# 3_shkb_downstream_con.net
KiCad netlist of a schematic drawn in Altium Designer
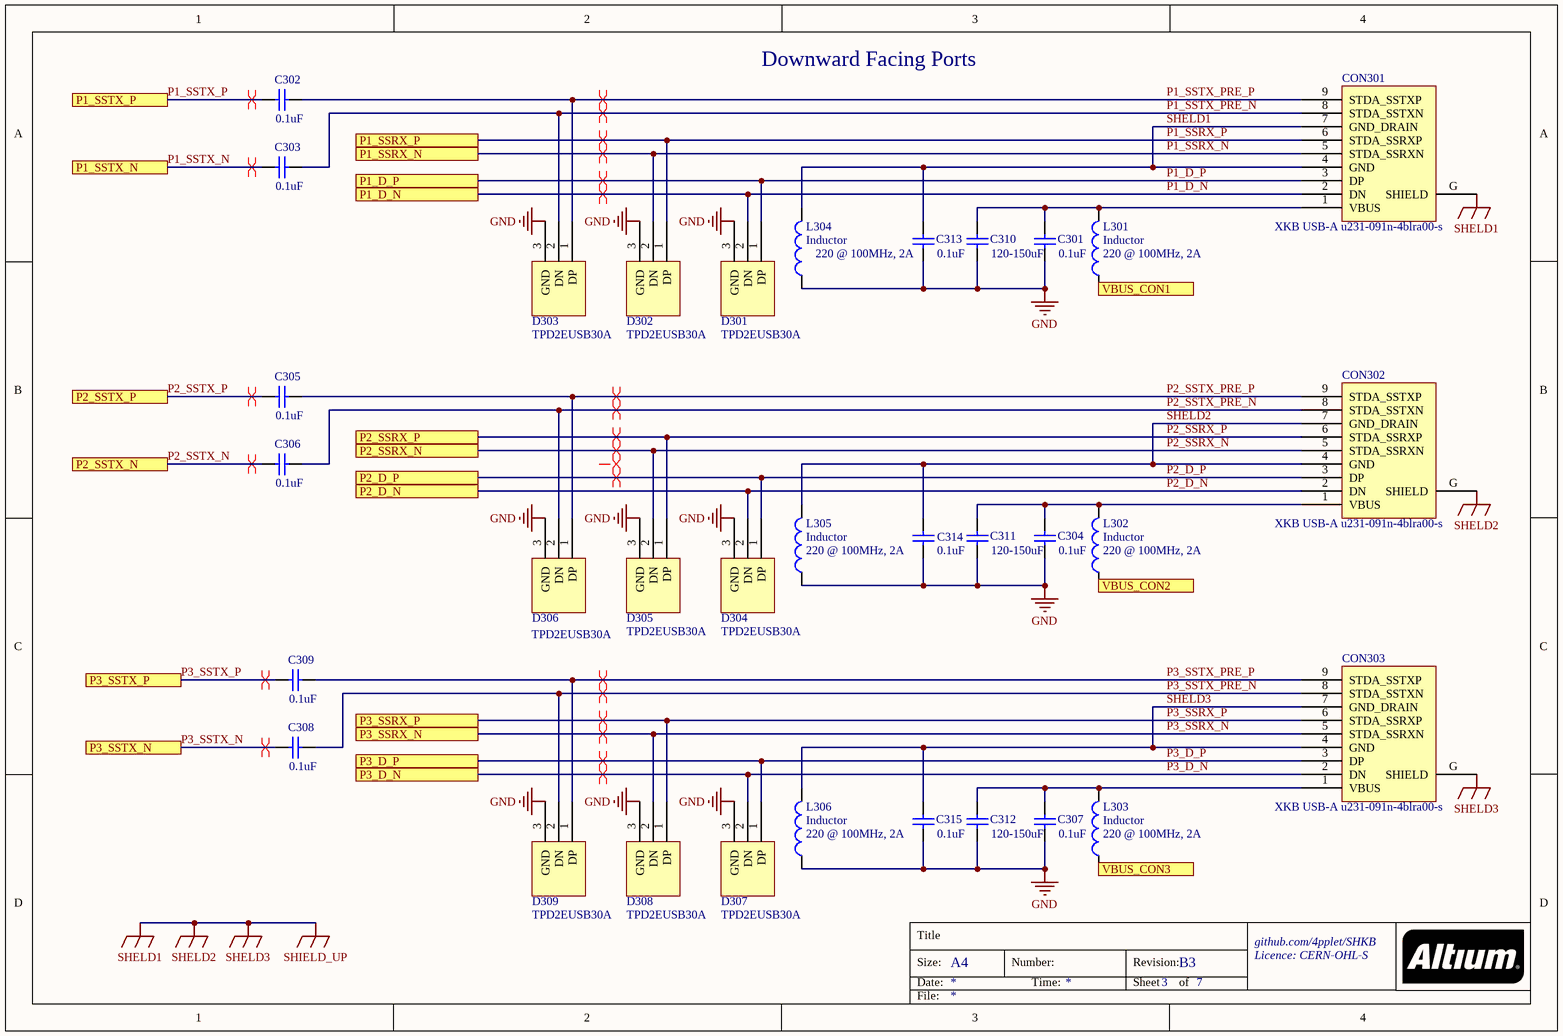
[diagram p0: 3_shkb_downstream_con.SchDoc]

(export (version "E")
  (design (tool "Eeschema 10.0.6"))
  (components
    (comp (ref "C301")
      (value "0.1uF")
      (footprint "C0603[1608]")
      (description "Capacitor")
      (fields (field (name "MFG") "KEMET") (field (name "LCSC PART #") "C14663"))
      (libsource (lib "Miscellaneous Devices") (part "Cap"))
    )
    (comp (ref "C302")
      (value "0.1uF")
      (footprint "C0402[1005]")
      (description "Capacitor")
      (fields (field (name "MFG") "KEMET") (field (name "LCSC PART #") "C1525"))
      (libsource (lib "Miscellaneous Devices") (part "Cap"))
    )
    (comp (ref "C303")
      (value "0.1uF")
      (footprint "C0402[1005]")
      (description "Capacitor")
      (fields (field (name "MFG") "KEMET") (field (name "LCSC PART #") "C1525"))
      (libsource (lib "Miscellaneous Devices") (part "Cap"))
    )
    (comp (ref "C304")
      (value "0.1uF")
      (footprint "C0603[1608]")
      (description "Capacitor")
      (fields (field (name "MFG") "KEMET") (field (name "LCSC PART #") "C14663"))
      (libsource (lib "Miscellaneous Devices") (part "Cap"))
    )
    (comp (ref "C305")
      (value "0.1uF")
      (footprint "C0402[1005]")
      (description "Capacitor")
      (fields (field (name "MFG") "KEMET") (field (name "LCSC PART #") "C1525"))
      (libsource (lib "Miscellaneous Devices") (part "Cap"))
    )
    (comp (ref "C306")
      (value "0.1uF")
      (footprint "C0402[1005]")
      (description "Capacitor")
      (fields (field (name "MFG") "KEMET") (field (name "LCSC PART #") "C1525"))
      (libsource (lib "Miscellaneous Devices") (part "Cap"))
    )
    (comp (ref "C307")
      (value "0.1uF")
      (footprint "C0603[1608]")
      (description "Capacitor")
      (fields (field (name "MFG") "KEMET") (field (name "LCSC PART #") "C14663"))
      (libsource (lib "Miscellaneous Devices") (part "Cap"))
    )
    (comp (ref "C308")
      (value "0.1uF")
      (footprint "C0402[1005]")
      (description "Capacitor")
      (fields (field (name "MFG") "KEMET") (field (name "LCSC PART #") "C1525"))
      (libsource (lib "Miscellaneous Devices") (part "Cap"))
    )
    (comp (ref "C309")
      (value "0.1uF")
      (footprint "C0402[1005]")
      (description "Capacitor")
      (fields (field (name "MFG") "KEMET") (field (name "LCSC PART #") "C1525"))
      (libsource (lib "Miscellaneous Devices") (part "Cap"))
    )
    (comp (ref "C310")
      (value "120-150uF")
      (footprint "C_9L_9M")
      (description "Capacitor")
      (fields (field (name "MRF.PART") "XT100UF16V90RV0074") (field (name "LCSC PART #") "C2992605"))
      (libsource (lib "Miscellaneous Devices") (part "Cap"))
    )
    (comp (ref "C311")
      (value "120-150uF")
      (footprint "C_9L_9M")
      (description "Capacitor")
      (fields (field (name "MRF.PART") "XT100UF16V90RV0074") (field (name "LCSC PART #") "C2992605"))
      (libsource (lib "Miscellaneous Devices") (part "Cap"))
    )
    (comp (ref "C312")
      (value "120-150uF")
      (footprint "C_9L_9M")
      (description "Capacitor")
      (fields (field (name "MRF.PART") "XT100UF16V90RV0074") (field (name "LCSC PART #") "C2992605"))
      (libsource (lib "Miscellaneous Devices") (part "Cap"))
    )
    (comp (ref "C313")
      (value "0.1uF")
      (footprint "C0603[1608]")
      (description "Capacitor")
      (fields (field (name "MFG") "KEMET") (field (name "LCSC PART #") "C14663"))
      (libsource (lib "Miscellaneous Devices") (part "Cap"))
    )
    (comp (ref "C314")
      (value "0.1uF")
      (footprint "C0603[1608]")
      (description "Capacitor")
      (fields (field (name "MFG") "KEMET") (field (name "LCSC PART #") "C14663"))
      (libsource (lib "Miscellaneous Devices") (part "Cap"))
    )
    (comp (ref "C315")
      (value "0.1uF")
      (footprint "C0603[1608]")
      (description "Capacitor")
      (fields (field (name "MFG") "KEMET") (field (name "LCSC PART #") "C14663"))
      (libsource (lib "Miscellaneous Devices") (part "Cap"))
    )
    (comp (ref "CON301")
      (value "XKB USB-A u231-091n-4blra00-s")
      (footprint "XKB USB-A u231-091n-4blra00-s")
      (fields (field (name "LCSC PART #") "C381140") (field (name "MRF.PART") "U231-091N-4BLRA00-S-1"))
      (libsource (lib "lib") (part "XKB USB-A u231-091n-4blra00-s"))
    )
    (comp (ref "CON302")
      (value "XKB USB-A u231-091n-4blra00-s")
      (footprint "XKB USB-A u231-091n-4blra00-s")
      (fields (field (name "LCSC PART #") "C381140") (field (name "MRF.PART") "U231-091N-4BLRA00-S-1"))
      (libsource (lib "lib") (part "XKB USB-A u231-091n-4blra00-s"))
    )
    (comp (ref "CON303")
      (value "XKB USB-A u231-091n-4blra00-s")
      (footprint "XKB USB-A u231-091n-4blra00-s")
      (fields (field (name "LCSC PART #") "C381140") (field (name "MRF.PART") "U231-091N-4BLRA00-S-1"))
      (libsource (lib "lib") (part "XKB USB-A u231-091n-4blra00-s"))
    )
    (comp (ref "D301")
      (value "TPD2EUSB30A")
      (footprint "TPD2EUSB30A")
      (fields
        (field (name "MFG") "Texas Instruments")
        (field (name "LCSC PART #") "C2844720")
        (field (name "MRF.PART") "TPD2EUSB30DRTR-TP")
      )
      (libsource (lib "lib") (part "TPD2EUSB30A"))
    )
    (comp (ref "D302")
      (value "TPD2EUSB30A")
      (footprint "TPD2EUSB30A")
      (fields
        (field (name "MFG") "Texas Instruments")
        (field (name "LCSC PART #") "C2844720")
        (field (name "MRF.PART") "TPD2EUSB30DRTR-TP")
      )
      (libsource (lib "lib") (part "TPD2EUSB30A"))
    )
    (comp (ref "D303")
      (value "TPD2EUSB30A")
      (footprint "TPD2EUSB30A")
      (fields
        (field (name "MFG") "Texas Instruments")
        (field (name "LCSC PART #") "C2844720")
        (field (name "MRF.PART") "TPD2EUSB30DRTR-TP")
      )
      (libsource (lib "lib") (part "TPD2EUSB30A"))
    )
    (comp (ref "D304")
      (value "TPD2EUSB30A")
      (footprint "TPD2EUSB30A")
      (fields
        (field (name "MFG") "Texas Instruments")
        (field (name "LCSC PART #") "C2844720")
        (field (name "MRF.PART") "TPD2EUSB30DRTR-TP")
      )
      (libsource (lib "lib") (part "TPD2EUSB30A"))
    )
    (comp (ref "D305")
      (value "TPD2EUSB30A")
      (footprint "TPD2EUSB30A")
      (fields
        (field (name "MFG") "Texas Instruments")
        (field (name "LCSC PART #") "C2844720")
        (field (name "MRF.PART") "TPD2EUSB30DRTR-TP")
      )
      (libsource (lib "lib") (part "TPD2EUSB30A"))
    )
    (comp (ref "D306")
      (value "TPD2EUSB30A")
      (footprint "TPD2EUSB30A")
      (fields
        (field (name "MFG") "Texas Instruments")
        (field (name "LCSC PART #") "C2844720")
        (field (name "MRF.PART") "TPD2EUSB30DRTR-TP")
      )
      (libsource (lib "lib") (part "TPD2EUSB30A"))
    )
    (comp (ref "D307")
      (value "TPD2EUSB30A")
      (footprint "TPD2EUSB30A")
      (fields
        (field (name "MFG") "Texas Instruments")
        (field (name "LCSC PART #") "C2844720")
        (field (name "MRF.PART") "TPD2EUSB30DRTR-TP")
      )
      (libsource (lib "lib") (part "TPD2EUSB30A"))
    )
    (comp (ref "D308")
      (value "TPD2EUSB30A")
      (footprint "TPD2EUSB30A")
      (fields
        (field (name "MFG") "Texas Instruments")
        (field (name "LCSC PART #") "C2844720")
        (field (name "MRF.PART") "TPD2EUSB30DRTR-TP")
      )
      (libsource (lib "lib") (part "TPD2EUSB30A"))
    )
    (comp (ref "D309")
      (value "TPD2EUSB30A")
      (footprint "TPD2EUSB30A")
      (fields
        (field (name "MFG") "Texas Instruments")
        (field (name "LCSC PART #") "C2844720")
        (field (name "MRF.PART") "TPD2EUSB30DRTR-TP")
      )
      (libsource (lib "lib") (part "TPD2EUSB30A"))
    )
    (comp (ref "L301")
      (value "Inductor")
      (footprint "L0603[1608]")
      (fields
        (field (name "ALTIUM_VALUE") "220 @ 100MHz, 2A")
        (field (name "MFG") "Murata Electronics North America")
        (field (name "LCSC PART #") "C85832")
        (field (name "MRF.PART") "BLM18KG331SN1D")
      )
      (libsource (lib "Miscellaneous Devices") (part "Inductor"))
    )
    (comp (ref "L302")
      (value "Inductor")
      (footprint "L0603[1608]")
      (fields
        (field (name "ALTIUM_VALUE") "220 @ 100MHz, 2A")
        (field (name "MFG") "Murata Electronics North America")
        (field (name "LCSC PART #") "C85832")
        (field (name "MRF.PART") "BLM18KG331SN1D")
      )
      (libsource (lib "Miscellaneous Devices") (part "Inductor"))
    )
    (comp (ref "L303")
      (value "Inductor")
      (footprint "L0603[1608]")
      (fields
        (field (name "ALTIUM_VALUE") "220 @ 100MHz, 2A")
        (field (name "MFG") "Murata Electronics North America")
        (field (name "LCSC PART #") "C85832")
        (field (name "MRF.PART") "BLM18KG331SN1D")
      )
      (libsource (lib "Miscellaneous Devices") (part "Inductor"))
    )
    (comp (ref "L304")
      (value "Inductor")
      (footprint "L0603[1608]")
      (fields
        (field (name "ALTIUM_VALUE") "220 @ 100MHz, 2A")
        (field (name "MFG") "Murata Electronics North America")
        (field (name "LCSC PART #") "C85832")
        (field (name "MRF.PART") "BLM18KG331SN1D")
      )
      (libsource (lib "Miscellaneous Devices") (part "Inductor"))
    )
    (comp (ref "L305")
      (value "Inductor")
      (footprint "L0603[1608]")
      (fields
        (field (name "ALTIUM_VALUE") "220 @ 100MHz, 2A")
        (field (name "MFG") "Murata Electronics North America")
        (field (name "LCSC PART #") "C85832")
        (field (name "MRF.PART") "BLM18KG331SN1D")
      )
      (libsource (lib "Miscellaneous Devices") (part "Inductor"))
    )
    (comp (ref "L306")
      (value "Inductor")
      (footprint "L0603[1608]")
      (fields
        (field (name "ALTIUM_VALUE") "220 @ 100MHz, 2A")
        (field (name "MFG") "Murata Electronics North America")
        (field (name "LCSC PART #") "C85832")
        (field (name "MRF.PART") "BLM18KG331SN1D")
      )
      (libsource (lib "Miscellaneous Devices") (part "Inductor"))
    )
  )
  (nets
    (net (code "1") (name "/P1_D_N") (class "Default")
      (node (ref "CON301") (pin "2") (pinfunction "DN_2") (pintype "passive"))
      (node (ref "D301") (pin "2") (pinfunction "DN_2") (pintype "passive"))
    )
    (net (code "2") (name "/P1_D_P") (class "Default")
      (node (ref "CON301") (pin "3") (pinfunction "DP_3") (pintype "passive"))
      (node (ref "D301") (pin "1") (pinfunction "DP_1") (pintype "passive"))
    )
    (net (code "3") (name "/P1_SSRX_N") (class "Default")
      (node (ref "CON301") (pin "5") (pinfunction "STDA_SSRXN_5") (pintype "passive"))
      (node (ref "D302") (pin "2") (pinfunction "DN_2") (pintype "passive"))
    )
    (net (code "4") (name "/P1_SSRX_P") (class "Default")
      (node (ref "CON301") (pin "6") (pinfunction "STDA_SSRXP_6") (pintype "passive"))
      (node (ref "D302") (pin "1") (pinfunction "DP_1") (pintype "passive"))
    )
    (net (code "5") (name "/P1_SSTX_N") (class "Default")
      (node (ref "C303") (pin "2") (pinfunction "2_2") (pintype "passive"))
    )
    (net (code "6") (name "/P1_SSTX_P") (class "Default")
      (node (ref "C302") (pin "2") (pinfunction "2_2") (pintype "passive"))
    )
    (net (code "7") (name "/P1_SSTX_PRE_N") (class "Default")
      (node (ref "C303") (pin "1") (pinfunction "1_1") (pintype "passive"))
      (node (ref "CON301") (pin "8") (pinfunction "STDA_SSTXN_8") (pintype "passive"))
      (node (ref "D303") (pin "2") (pinfunction "DN_2") (pintype "passive"))
    )
    (net (code "8") (name "/P1_SSTX_PRE_P") (class "Default")
      (node (ref "C302") (pin "1") (pinfunction "1_1") (pintype "passive"))
      (node (ref "CON301") (pin "9") (pinfunction "STDA_SSTXP_9") (pintype "passive"))
      (node (ref "D303") (pin "1") (pinfunction "DP_1") (pintype "passive"))
    )
    (net (code "9") (name "/P2_D_N") (class "Default")
      (node (ref "CON302") (pin "2") (pinfunction "DN_2") (pintype "passive"))
      (node (ref "D304") (pin "2") (pinfunction "DN_2") (pintype "passive"))
    )
    (net (code "10") (name "/P2_D_P") (class "Default")
      (node (ref "CON302") (pin "3") (pinfunction "DP_3") (pintype "passive"))
      (node (ref "D304") (pin "1") (pinfunction "DP_1") (pintype "passive"))
    )
    (net (code "11") (name "/P2_SSRX_N") (class "Default")
      (node (ref "CON302") (pin "5") (pinfunction "STDA_SSRXN_5") (pintype "passive"))
      (node (ref "D305") (pin "2") (pinfunction "DN_2") (pintype "passive"))
    )
    (net (code "12") (name "/P2_SSRX_P") (class "Default")
      (node (ref "CON302") (pin "6") (pinfunction "STDA_SSRXP_6") (pintype "passive"))
      (node (ref "D305") (pin "1") (pinfunction "DP_1") (pintype "passive"))
    )
    (net (code "13") (name "/P2_SSTX_N") (class "Default")
      (node (ref "C306") (pin "1") (pinfunction "1_1") (pintype "passive"))
    )
    (net (code "14") (name "/P2_SSTX_P") (class "Default")
      (node (ref "C305") (pin "1") (pinfunction "1_1") (pintype "passive"))
    )
    (net (code "15") (name "/P2_SSTX_PRE_N") (class "Default")
      (node (ref "C306") (pin "2") (pinfunction "2_2") (pintype "passive"))
      (node (ref "CON302") (pin "8") (pinfunction "STDA_SSTXN_8") (pintype "passive"))
      (node (ref "D306") (pin "2") (pinfunction "DN_2") (pintype "passive"))
    )
    (net (code "16") (name "/P2_SSTX_PRE_P") (class "Default")
      (node (ref "C305") (pin "2") (pinfunction "2_2") (pintype "passive"))
      (node (ref "CON302") (pin "9") (pinfunction "STDA_SSTXP_9") (pintype "passive"))
      (node (ref "D306") (pin "1") (pinfunction "DP_1") (pintype "passive"))
    )
    (net (code "17") (name "/P3_D_N") (class "Default")
      (node (ref "CON303") (pin "2") (pinfunction "DN_2") (pintype "passive"))
      (node (ref "D307") (pin "2") (pinfunction "DN_2") (pintype "passive"))
    )
    (net (code "18") (name "/P3_D_P") (class "Default")
      (node (ref "CON303") (pin "3") (pinfunction "DP_3") (pintype "passive"))
      (node (ref "D307") (pin "1") (pinfunction "DP_1") (pintype "passive"))
    )
    (net (code "19") (name "/P3_SSRX_N") (class "Default")
      (node (ref "CON303") (pin "5") (pinfunction "STDA_SSRXN_5") (pintype "passive"))
      (node (ref "D308") (pin "2") (pinfunction "DN_2") (pintype "passive"))
    )
    (net (code "20") (name "/P3_SSRX_P") (class "Default")
      (node (ref "CON303") (pin "6") (pinfunction "STDA_SSRXP_6") (pintype "passive"))
      (node (ref "D308") (pin "1") (pinfunction "DP_1") (pintype "passive"))
    )
    (net (code "21") (name "/P3_SSTX_N") (class "Default")
      (node (ref "C308") (pin "1") (pinfunction "1_1") (pintype "passive"))
    )
    (net (code "22") (name "/P3_SSTX_P") (class "Default")
      (node (ref "C309") (pin "1") (pinfunction "1_1") (pintype "passive"))
    )
    (net (code "23") (name "/P3_SSTX_PRE_N") (class "Default")
      (node (ref "C308") (pin "2") (pinfunction "2_2") (pintype "passive"))
      (node (ref "CON303") (pin "8") (pinfunction "STDA_SSTXN_8") (pintype "passive"))
      (node (ref "D309") (pin "2") (pinfunction "DN_2") (pintype "passive"))
    )
    (net (code "24") (name "/P3_SSTX_PRE_P") (class "Default")
      (node (ref "C309") (pin "2") (pinfunction "2_2") (pintype "passive"))
      (node (ref "CON303") (pin "9") (pinfunction "STDA_SSTXP_9") (pintype "passive"))
      (node (ref "D309") (pin "1") (pinfunction "DP_1") (pintype "passive"))
    )
    (net (code "25") (name "/VBUS_CON1") (class "Default")
      (node (ref "L301") (pin "1") (pinfunction "1_1") (pintype "passive"))
    )
    (net (code "26") (name "/VBUS_CON2") (class "Default")
      (node (ref "L302") (pin "1") (pinfunction "1_1") (pintype "passive"))
    )
    (net (code "27") (name "/VBUS_CON3") (class "Default")
      (node (ref "L303") (pin "1") (pinfunction "1_1") (pintype "passive"))
    )
    (net (code "28") (name "GND") (class "Default")
      (node (ref "C301") (pin "1") (pinfunction "1_1") (pintype "passive"))
      (node (ref "C304") (pin "1") (pinfunction "1_1") (pintype "passive"))
      (node (ref "C307") (pin "1") (pinfunction "1_1") (pintype "passive"))
      (node (ref "C310") (pin "1") (pinfunction "1_1") (pintype "passive"))
      (node (ref "C311") (pin "1") (pinfunction "1_1") (pintype "passive"))
      (node (ref "C312") (pin "1") (pinfunction "1_1") (pintype "passive"))
      (node (ref "C313") (pin "1") (pinfunction "1_1") (pintype "passive"))
      (node (ref "C314") (pin "1") (pinfunction "1_1") (pintype "passive"))
      (node (ref "C315") (pin "1") (pinfunction "1_1") (pintype "passive"))
      (node (ref "D301") (pin "3") (pinfunction "GND_3") (pintype "passive"))
      (node (ref "D302") (pin "3") (pinfunction "GND_3") (pintype "passive"))
      (node (ref "D303") (pin "3") (pinfunction "GND_3") (pintype "passive"))
      (node (ref "D304") (pin "3") (pinfunction "GND_3") (pintype "passive"))
      (node (ref "D305") (pin "3") (pinfunction "GND_3") (pintype "passive"))
      (node (ref "D306") (pin "3") (pinfunction "GND_3") (pintype "passive"))
      (node (ref "D307") (pin "3") (pinfunction "GND_3") (pintype "passive"))
      (node (ref "D308") (pin "3") (pinfunction "GND_3") (pintype "passive"))
      (node (ref "D309") (pin "3") (pinfunction "GND_3") (pintype "passive"))
      (node (ref "L304") (pin "1") (pinfunction "1_1") (pintype "passive"))
      (node (ref "L305") (pin "1") (pinfunction "1_1") (pintype "passive"))
      (node (ref "L306") (pin "1") (pinfunction "1_1") (pintype "passive"))
    )
    (net (code "29") (name "Net-(CON301-VBUS)") (class "Default")
      (node (ref "C301") (pin "2") (pinfunction "2_2") (pintype "passive"))
      (node (ref "C310") (pin "2") (pinfunction "2_2") (pintype "passive"))
      (node (ref "CON301") (pin "1") (pinfunction "VBUS_1") (pintype "passive"))
      (node (ref "L301") (pin "2") (pinfunction "2_2") (pintype "passive"))
    )
    (net (code "30") (name "Net-(CON302-VBUS)") (class "Default")
      (node (ref "C304") (pin "2") (pinfunction "2_2") (pintype "passive"))
      (node (ref "C311") (pin "2") (pinfunction "2_2") (pintype "passive"))
      (node (ref "CON302") (pin "1") (pinfunction "VBUS_1") (pintype "passive"))
      (node (ref "L302") (pin "2") (pinfunction "2_2") (pintype "passive"))
    )
    (net (code "31") (name "Net-(CON303-VBUS)") (class "Default")
      (node (ref "C307") (pin "2") (pinfunction "2_2") (pintype "passive"))
      (node (ref "C312") (pin "2") (pinfunction "2_2") (pintype "passive"))
      (node (ref "CON303") (pin "1") (pinfunction "VBUS_1") (pintype "passive"))
      (node (ref "L303") (pin "2") (pinfunction "2_2") (pintype "passive"))
    )
    (net (code "32") (name "SHELD1") (class "Default")
      (node (ref "C313") (pin "2") (pinfunction "2_2") (pintype "passive"))
      (node (ref "C314") (pin "2") (pinfunction "2_2") (pintype "passive"))
      (node (ref "C315") (pin "2") (pinfunction "2_2") (pintype "passive"))
      (node (ref "CON301") (pin "4") (pinfunction "GND_4") (pintype "passive"))
      (node (ref "CON301") (pin "7") (pinfunction "GND_DRAIN_7") (pintype "passive"))
      (node (ref "CON301") (pin "G") (pinfunction "SHIELD_G") (pintype "passive"))
      (node (ref "CON302") (pin "4") (pinfunction "GND_4") (pintype "passive"))
      (node (ref "CON302") (pin "7") (pinfunction "GND_DRAIN_7") (pintype "passive"))
      (node (ref "CON302") (pin "G") (pinfunction "SHIELD_G") (pintype "passive"))
      (node (ref "CON303") (pin "4") (pinfunction "GND_4") (pintype "passive"))
      (node (ref "CON303") (pin "7") (pinfunction "GND_DRAIN_7") (pintype "passive"))
      (node (ref "CON303") (pin "G") (pinfunction "SHIELD_G") (pintype "passive"))
      (node (ref "L304") (pin "2") (pinfunction "2_2") (pintype "passive"))
      (node (ref "L305") (pin "2") (pinfunction "2_2") (pintype "passive"))
      (node (ref "L306") (pin "2") (pinfunction "2_2") (pintype "passive"))
    )
  )
)
